# RGBLED.net
KiCad netlist of a schematic drawn in Altium Designer
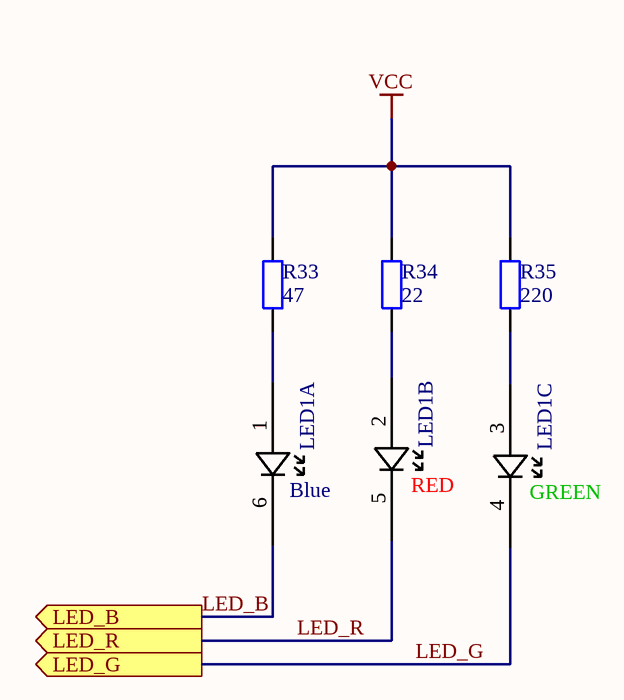
[diagram p0: RGBLED.SchDoc]

(export (version "E")
  (design (tool "Eeschema 10.0.6"))
  (components
    (comp (ref "LED1")
      (value "LED_Red_Blue_Green")
      (footprint "SMLP36")
      (description "PICOLED, Rouge, Vert, Bleu, CMS, Rectangulaire, R 5mA, G 5mA, B 5mA")
      (libsource (lib "ComponentLib") (part "LED_Red_Blue_Green"))
    )
    (comp (ref "R33")
      (value "47")
      (footprint "RES 0603/1608")
      (libsource (lib "Miscellaneous Devices") (part "Res2"))
    )
    (comp (ref "R34")
      (value "22")
      (footprint "RES 0603/1608")
      (libsource (lib "Miscellaneous Devices") (part "Res2"))
    )
    (comp (ref "R35")
      (value "220")
      (footprint "RES 0603/1608")
      (libsource (lib "Miscellaneous Devices") (part "Res2"))
    )
  )
  (nets
    (net (code "1") (name "/LED_B") (class "Default")
      (node (ref "LED1") (pin "6") (pinfunction "6_6") (pintype "passive"))
    )
    (net (code "2") (name "/LED_G") (class "Default")
      (node (ref "LED1") (pin "4") (pinfunction "4_4") (pintype "passive"))
    )
    (net (code "3") (name "/LED_R") (class "Default")
      (node (ref "LED1") (pin "5") (pinfunction "5_5") (pintype "passive"))
    )
    (net (code "4") (name "Net-(LED1-Pad1)") (class "Default")
      (node (ref "LED1") (pin "1") (pinfunction "1_1") (pintype "passive"))
      (node (ref "R33") (pin "1") (pinfunction "1_1") (pintype "passive"))
    )
    (net (code "5") (name "Net-(LED1-Pad2)") (class "Default")
      (node (ref "LED1") (pin "2") (pinfunction "2_2") (pintype "passive"))
      (node (ref "R34") (pin "1") (pinfunction "1_1") (pintype "passive"))
    )
    (net (code "6") (name "Net-(LED1-Pad3)") (class "Default")
      (node (ref "LED1") (pin "3") (pinfunction "3_3") (pintype "passive"))
      (node (ref "R35") (pin "1") (pinfunction "1_1") (pintype "passive"))
    )
    (net (code "7") (name "VCC") (class "Default")
      (node (ref "R33") (pin "2") (pinfunction "2_2") (pintype "passive"))
      (node (ref "R34") (pin "2") (pinfunction "2_2") (pintype "passive"))
      (node (ref "R35") (pin "2") (pinfunction "2_2") (pintype "passive"))
    )
  )
)
